# SCH_tec-APUS_7_2022-02-12.net
KiCad netlist of a schematic drawn in EasyEDA
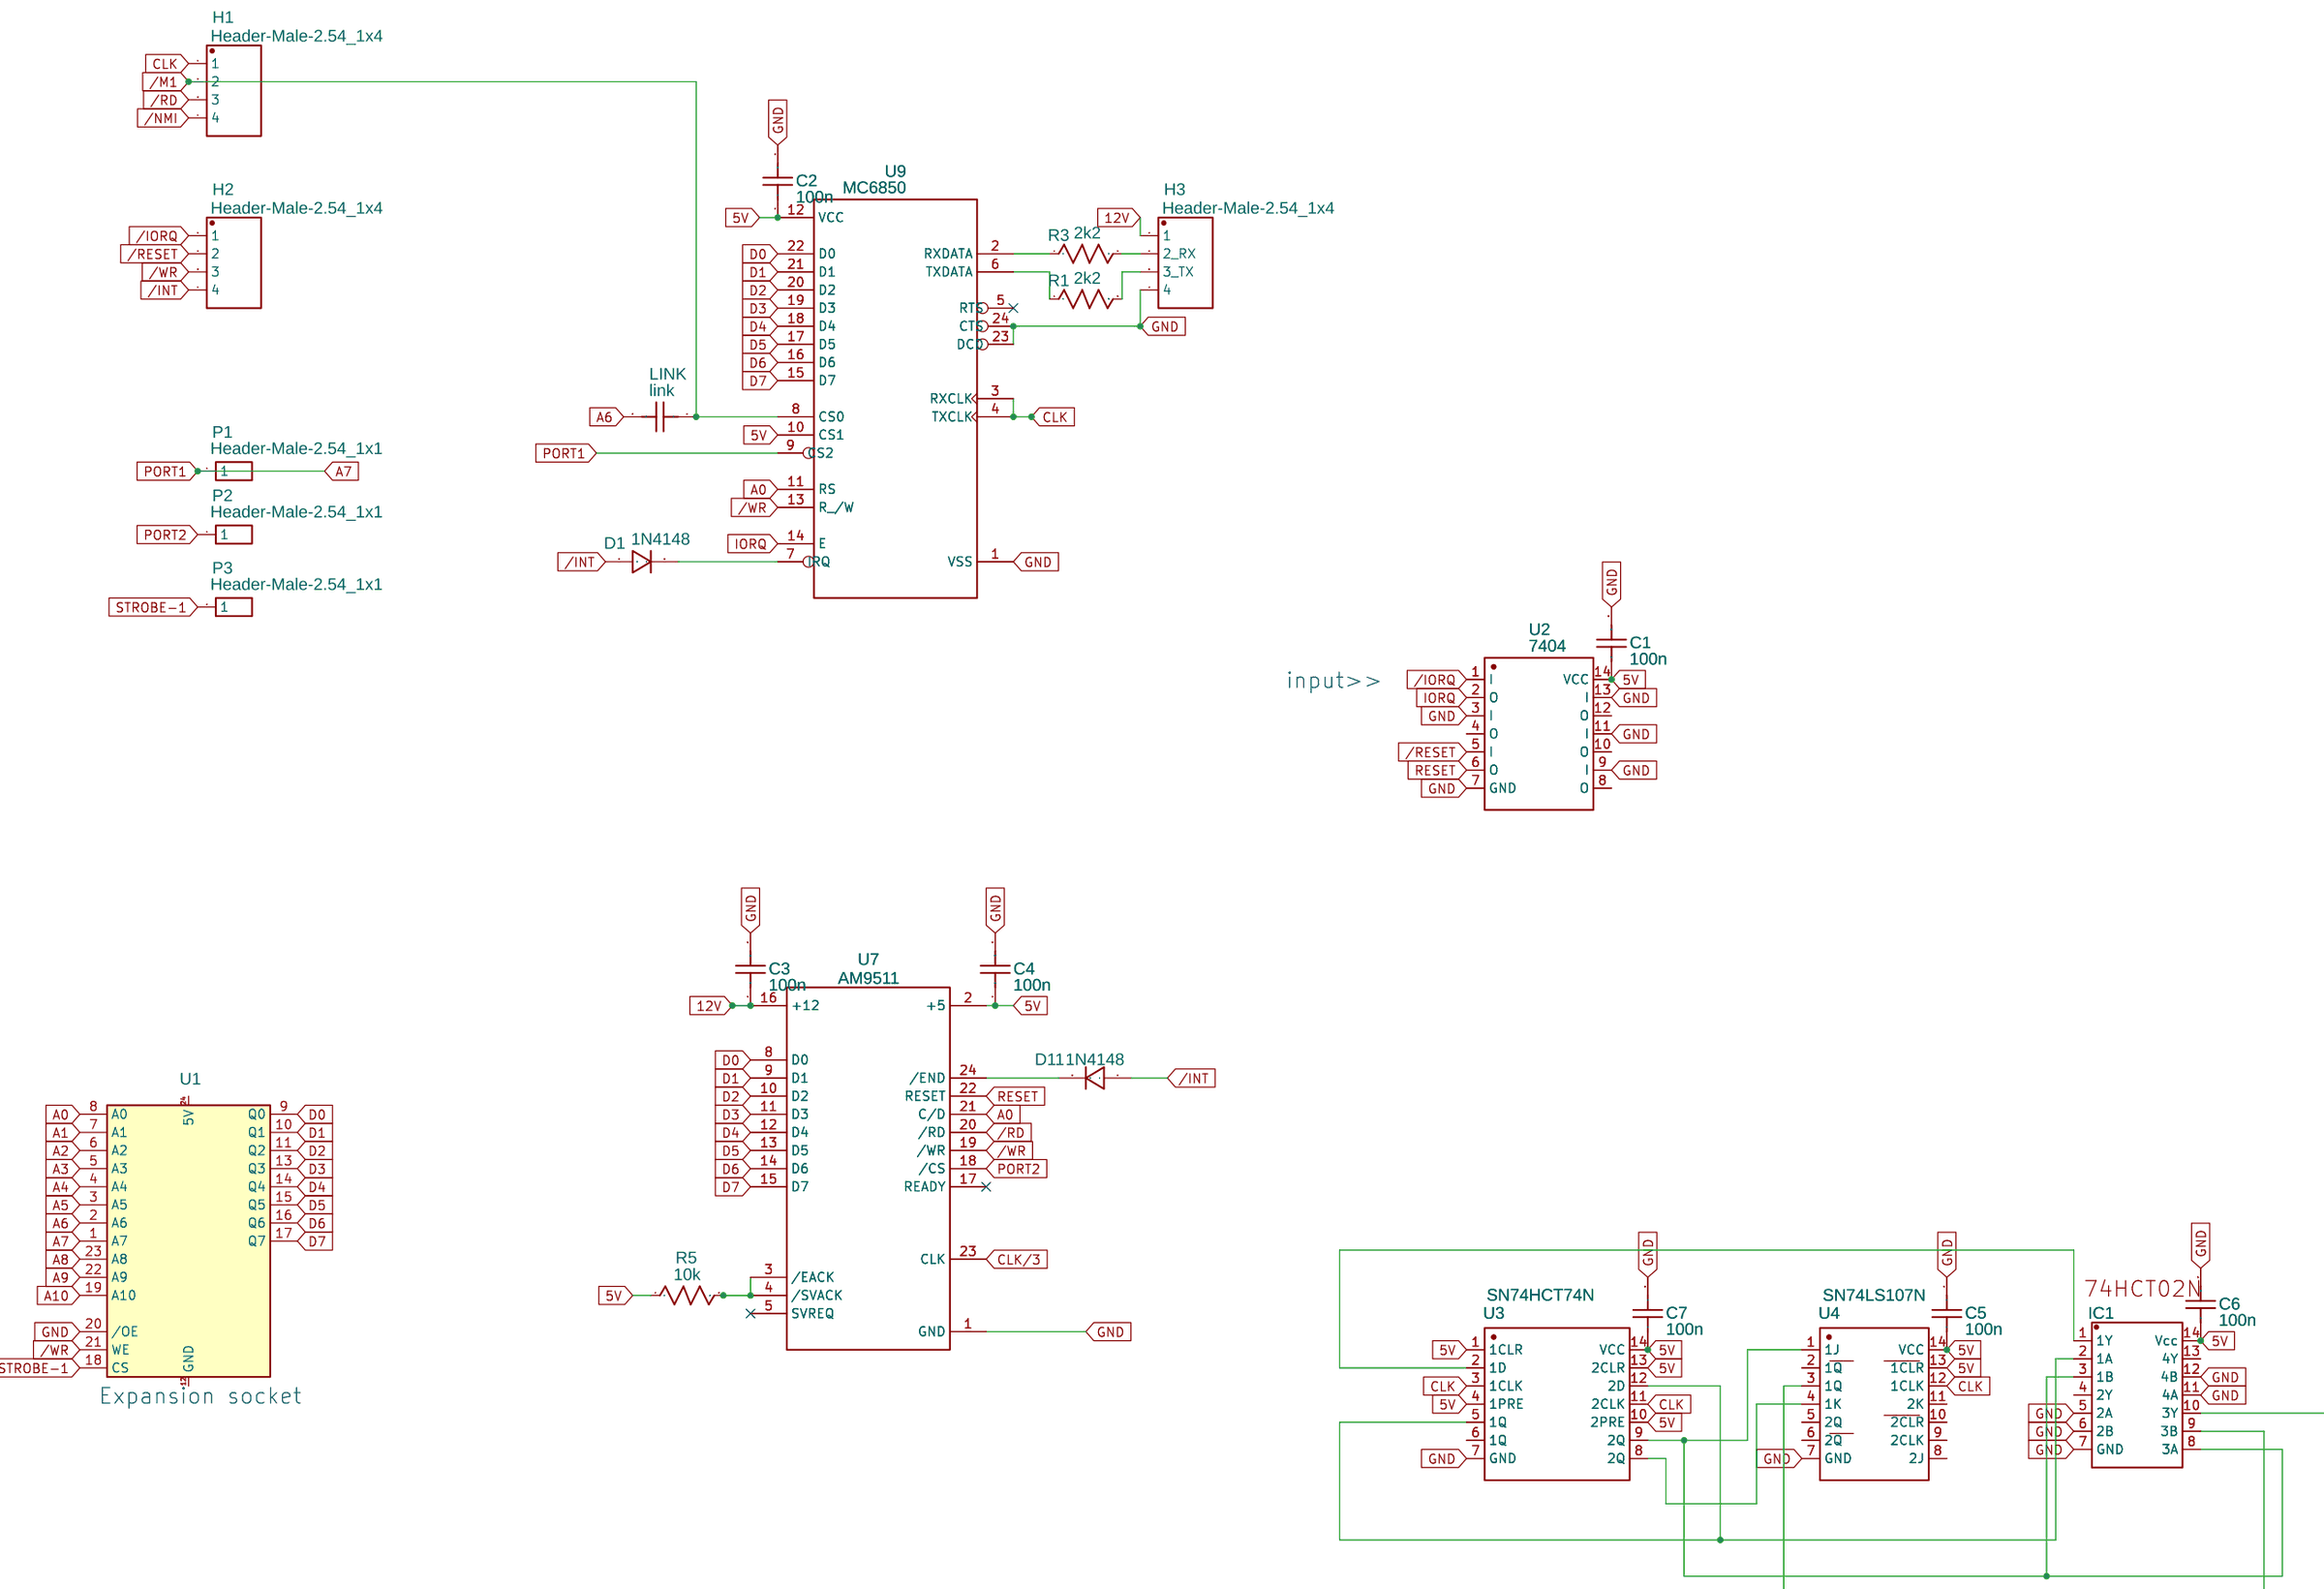
[diagram p0: schematic sheet]

(export (version "E")
  (design (tool "Eeschema 10.0.6"))
  (components
    (comp (ref "C1") (value "100n") (libsource (lib "") (part "C_RAD-0.1_US_1")))
    (comp (ref "C2") (value "100n") (libsource (lib "") (part "C_RAD-0.1_US_1")))
    (comp (ref "C3") (value "100n") (libsource (lib "") (part "C_RAD-0.1_US_1")))
    (comp (ref "C4") (value "100n") (libsource (lib "") (part "C_RAD-0.1_US_1")))
    (comp (ref "C5") (value "100n") (libsource (lib "") (part "C_RAD-0.1_US_1")))
    (comp (ref "C6") (value "100n") (libsource (lib "") (part "C_RAD-0.1_US_1")))
    (comp (ref "C7") (value "100n") (libsource (lib "") (part "C_RAD-0.1_US_1")))
    (comp (ref "D1")
      (value "1N4148")
      (fields (field (name "BOM_Manufacturer Part") "1N4448") (field (name "BOM_Supplier Part") "C54037"))
      (libsource (lib "") (part "Unknown_490_-415"))
    )
    (comp (ref "D11")
      (value "1N4148")
      (fields (field (name "BOM_Manufacturer Part") "1N4448") (field (name "BOM_Supplier Part") "C54037"))
      (libsource (lib "") (part "Unknown_740_-130"))
    )
    (comp (ref "H1")
      (value "Header-Male-2.54_1x4")
      (fields
        (field (name "BOM_Manufacturer Part") "210S-1*4P L=11.6MMGold-plated black")
        (field (name "BOM_Supplier Part") "C124378")
      )
      (libsource (lib "") (part "Header-Male-2.54_1x4"))
    )
    (comp (ref "H2")
      (value "Header-Male-2.54_1x4")
      (fields
        (field (name "BOM_Manufacturer Part") "210S-1*4P L=11.6MMGold-plated black")
        (field (name "BOM_Supplier Part") "C124378")
      )
      (libsource (lib "") (part "Header-Male-2.54_1x4"))
    )
    (comp (ref "H3")
      (value "Header-Male-2.54_1x4")
      (fields
        (field (name "BOM_Manufacturer Part") "210S-1*4P L=11.6MMGold-plated black")
        (field (name "BOM_Supplier Part") "C124378")
      )
      (libsource (lib "") (part "Header-Male-2.54_1x4_1"))
    )
    (comp (ref "IC1") (value "x74HCT02N") (libsource (lib "") (part "x74HCT02N")))
    (comp (ref "LINK") (value "link") (libsource (lib "") (part "C_RAD-0.1_US")))
    (comp (ref "P1")
      (value "Header-Male-2.54_1x1")
      (fields (field (name "BOM_Supplier Part") "C81276"))
      (libsource (lib "") (part "Header-Male-2.54_1x1"))
    )
    (comp (ref "P2")
      (value "Header-Male-2.54_1x1")
      (fields (field (name "BOM_Supplier Part") "C81276"))
      (libsource (lib "") (part "Header-Male-2.54_1x1"))
    )
    (comp (ref "P3")
      (value "Header-Male-2.54_1x1")
      (fields (field (name "BOM_Supplier Part") "C81276"))
      (libsource (lib "") (part "Header-Male-2.54_1x1"))
    )
    (comp (ref "R1") (value "2k2") (libsource (lib "") (part "R_AXIAL-0.3_US")))
    (comp (ref "R3") (value "2k2") (libsource (lib "") (part "R_AXIAL-0.3_US")))
    (comp (ref "R5") (value "10k") (libsource (lib "") (part "R_AXIAL-0.3_US")))
    (comp (ref "U1")
      (value "6116")
      (fields (field (name "BOM_Manufacturer Part") "?"))
      (libsource (lib "") (part "Unknown_240_-40"))
    )
    (comp (ref "U2") (value "7404") (libsource (lib "") (part "7404")))
    (comp (ref "U3") (value "SN74HCT74N") (libsource (lib "") (part "SN74HCT74N")))
    (comp (ref "U4")
      (value "SN74LS107N")
      (fields (field (name "BOM_Supplier Part") "C5262"))
      (libsource (lib "") (part "SN74LS107N"))
    )
    (comp (ref "U7") (value "AM9511") (libsource (lib "") (part "AM9511")))
    (comp (ref "U9")
      (value "MC6850")
      (fields (field (name "BOM_Manufacturer Part") "?"))
      (libsource (lib "") (part "Unknown_635_-505"))
    )
  )
  (nets
    (net (code "1") (name "5V") (class "Default")
      (node (ref "C1") (pin "1") (pinfunction "1_1") (pintype "unspecified"))
      (node (ref "C2") (pin "1") (pinfunction "1_1") (pintype "unspecified"))
      (node (ref "C4") (pin "1") (pinfunction "1_1") (pintype "unspecified"))
      (node (ref "C5") (pin "1") (pinfunction "1_1") (pintype "unspecified"))
      (node (ref "C6") (pin "1") (pinfunction "1_1") (pintype "unspecified"))
      (node (ref "C7") (pin "1") (pinfunction "1_1") (pintype "unspecified"))
      (node (ref "IC1") (pin "14") (pinfunction "Vcc_14") (pintype "unspecified"))
      (node (ref "R5") (pin "1") (pinfunction "1_1") (pintype "unspecified"))
      (node (ref "U2") (pin "14") (pinfunction "VCC_14") (pintype "unspecified"))
      (node (ref "U3") (pin "1") (pinfunction "1CLR_1") (pintype "unspecified"))
      (node (ref "U3") (pin "10") (pinfunction "2PRE_10") (pintype "unspecified"))
      (node (ref "U3") (pin "13") (pinfunction "2CLR_13") (pintype "unspecified"))
      (node (ref "U3") (pin "14") (pinfunction "VCC_14") (pintype "unspecified"))
      (node (ref "U3") (pin "4") (pinfunction "1PRE_4") (pintype "unspecified"))
      (node (ref "U4") (pin "13") (pinfunction "1CLR_13") (pintype "unspecified"))
      (node (ref "U4") (pin "14") (pinfunction "VCC_14") (pintype "unspecified"))
      (node (ref "U7") (pin "2") (pinfunction "+5_2") (pintype "unspecified"))
      (node (ref "U9") (pin "10") (pinfunction "CS1_10") (pintype "input"))
      (node (ref "U9") (pin "12") (pinfunction "VCC_12") (pintype "passive"))
    )
    (net (code "2") (name "12V") (class "Default")
      (node (ref "C3") (pin "1") (pinfunction "1_1") (pintype "unspecified"))
      (node (ref "H3") (pin "1") (pinfunction "1_1") (pintype "unspecified"))
      (node (ref "U7") (pin "16") (pinfunction "+12_16") (pintype "unspecified"))
    )
    (net (code "3") (name "A0") (class "Default")
      (node (ref "U1") (pin "8") (pinfunction "A0_8") (pintype "input"))
      (node (ref "U7") (pin "21") (pinfunction "C/D_21") (pintype "unspecified"))
      (node (ref "U9") (pin "11") (pinfunction "RS_11") (pintype "input"))
    )
    (net (code "4") (name "A1") (class "Default")
      (node (ref "U1") (pin "7") (pinfunction "A1_7") (pintype "input"))
    )
    (net (code "5") (name "A2") (class "Default")
      (node (ref "U1") (pin "6") (pinfunction "A2_6") (pintype "input"))
    )
    (net (code "6") (name "A3") (class "Default")
      (node (ref "U1") (pin "5") (pinfunction "A3_5") (pintype "input"))
    )
    (net (code "7") (name "A4") (class "Default")
      (node (ref "U1") (pin "4") (pinfunction "A4_4") (pintype "input"))
    )
    (net (code "8") (name "A5") (class "Default")
      (node (ref "U1") (pin "3") (pinfunction "A5_3") (pintype "input"))
    )
    (net (code "9") (name "A6") (class "Default")
      (node (ref "LINK") (pin "2") (pinfunction "2_2") (pintype "unspecified"))
      (node (ref "U1") (pin "2") (pinfunction "A6_2") (pintype "input"))
    )
    (net (code "10") (name "A7") (class "Default")
      (node (ref "P1") (pin "1") (pinfunction "1_1") (pintype "input"))
      (node (ref "U1") (pin "1") (pinfunction "A7_1") (pintype "input"))
      (node (ref "U9") (pin "9") (pinfunction "CS2_9") (pintype "input"))
    )
    (net (code "11") (name "A8") (class "Default")
      (node (ref "U1") (pin "23") (pinfunction "A8_23") (pintype "input"))
    )
    (net (code "12") (name "A9") (class "Default")
      (node (ref "U1") (pin "22") (pinfunction "A9_22") (pintype "input"))
    )
    (net (code "13") (name "A10") (class "Default")
      (node (ref "U1") (pin "19") (pinfunction "A10_19") (pintype "input"))
    )
    (net (code "14") (name "CLK") (class "Default")
      (node (ref "H1") (pin "1") (pinfunction "1_1") (pintype "unspecified"))
      (node (ref "U3") (pin "11") (pinfunction "2CLK_11") (pintype "unspecified"))
      (node (ref "U3") (pin "3") (pinfunction "1CLK_3") (pintype "unspecified"))
      (node (ref "U4") (pin "12") (pinfunction "1CLK_12") (pintype "unspecified"))
      (node (ref "U9") (pin "3") (pinfunction "RXCLK_3") (pintype "input"))
      (node (ref "U9") (pin "4") (pinfunction "TXCLK_4") (pintype "input"))
    )
    (net (code "15") (name "CLK{slash}3") (class "Default")
      (node (ref "IC1") (pin "10") (pinfunction "3Y_10") (pintype "unspecified"))
      (node (ref "U7") (pin "23") (pinfunction "CLK_23") (pintype "unspecified"))
    )
    (net (code "16") (name "D0") (class "Default")
      (node (ref "U1") (pin "9") (pinfunction "Q0_9") (pintype "bidirectional"))
      (node (ref "U7") (pin "8") (pinfunction "D0_8") (pintype "unspecified"))
      (node (ref "U9") (pin "22") (pinfunction "D0_22") (pintype "unspecified"))
    )
    (net (code "17") (name "D1") (class "Default")
      (node (ref "U1") (pin "10") (pinfunction "Q1_10") (pintype "bidirectional"))
      (node (ref "U7") (pin "9") (pinfunction "D1_9") (pintype "unspecified"))
      (node (ref "U9") (pin "21") (pinfunction "D1_21") (pintype "unspecified"))
    )
    (net (code "18") (name "D2") (class "Default")
      (node (ref "U1") (pin "11") (pinfunction "Q2_11") (pintype "bidirectional"))
      (node (ref "U7") (pin "10") (pinfunction "D2_10") (pintype "unspecified"))
      (node (ref "U9") (pin "20") (pinfunction "D2_20") (pintype "unspecified"))
    )
    (net (code "19") (name "D3") (class "Default")
      (node (ref "U1") (pin "13") (pinfunction "Q3_13") (pintype "bidirectional"))
      (node (ref "U7") (pin "11") (pinfunction "D3_11") (pintype "unspecified"))
      (node (ref "U9") (pin "19") (pinfunction "D3_19") (pintype "unspecified"))
    )
    (net (code "20") (name "D4") (class "Default")
      (node (ref "U1") (pin "14") (pinfunction "Q4_14") (pintype "bidirectional"))
      (node (ref "U7") (pin "12") (pinfunction "D4_12") (pintype "unspecified"))
      (node (ref "U9") (pin "18") (pinfunction "D4_18") (pintype "unspecified"))
    )
    (net (code "21") (name "D5") (class "Default")
      (node (ref "U1") (pin "15") (pinfunction "Q5_15") (pintype "bidirectional"))
      (node (ref "U7") (pin "13") (pinfunction "D5_13") (pintype "unspecified"))
      (node (ref "U9") (pin "17") (pinfunction "D5_17") (pintype "unspecified"))
    )
    (net (code "22") (name "D6") (class "Default")
      (node (ref "U1") (pin "16") (pinfunction "Q6_16") (pintype "bidirectional"))
      (node (ref "U7") (pin "14") (pinfunction "D6_14") (pintype "unspecified"))
      (node (ref "U9") (pin "16") (pinfunction "D6_16") (pintype "unspecified"))
    )
    (net (code "23") (name "D7") (class "Default")
      (node (ref "U1") (pin "17") (pinfunction "Q7_17") (pintype "bidirectional"))
      (node (ref "U7") (pin "15") (pinfunction "D7_15") (pintype "unspecified"))
      (node (ref "U9") (pin "15") (pinfunction "D7_15") (pintype "unspecified"))
    )
    (net (code "24") (name "GND") (class "Default")
      (node (ref "C1") (pin "2") (pinfunction "2_2") (pintype "unspecified"))
      (node (ref "C2") (pin "2") (pinfunction "2_2") (pintype "unspecified"))
      (node (ref "C3") (pin "2") (pinfunction "2_2") (pintype "unspecified"))
      (node (ref "C4") (pin "2") (pinfunction "2_2") (pintype "unspecified"))
      (node (ref "C5") (pin "2") (pinfunction "2_2") (pintype "unspecified"))
      (node (ref "C6") (pin "2") (pinfunction "2_2") (pintype "unspecified"))
      (node (ref "C7") (pin "2") (pinfunction "2_2") (pintype "unspecified"))
      (node (ref "H3") (pin "4") (pinfunction "4_4") (pintype "unspecified"))
      (node (ref "IC1") (pin "11") (pinfunction "4A_11") (pintype "unspecified"))
      (node (ref "IC1") (pin "12") (pinfunction "4B_12") (pintype "unspecified"))
      (node (ref "IC1") (pin "5") (pinfunction "2A_5") (pintype "unspecified"))
      (node (ref "IC1") (pin "6") (pinfunction "2B_6") (pintype "unspecified"))
      (node (ref "IC1") (pin "7") (pinfunction "GND_7") (pintype "unspecified"))
      (node (ref "U1") (pin "20") (pinfunction "/OE_20") (pintype "input"))
      (node (ref "U2") (pin "11") (pinfunction "I_11") (pintype "unspecified"))
      (node (ref "U2") (pin "13") (pinfunction "I_13") (pintype "unspecified"))
      (node (ref "U2") (pin "3") (pinfunction "I_3") (pintype "unspecified"))
      (node (ref "U2") (pin "7") (pinfunction "GND_7") (pintype "unspecified"))
      (node (ref "U2") (pin "9") (pinfunction "I_9") (pintype "unspecified"))
      (node (ref "U3") (pin "7") (pinfunction "GND_7") (pintype "unspecified"))
      (node (ref "U4") (pin "7") (pinfunction "GND_7") (pintype "unspecified"))
      (node (ref "U7") (pin "1") (pinfunction "GND_1") (pintype "unspecified"))
      (node (ref "U9") (pin "1") (pinfunction "VSS_1") (pintype "passive"))
      (node (ref "U9") (pin "23") (pinfunction "DCD_23") (pintype "input"))
      (node (ref "U9") (pin "24") (pinfunction "CTS_24") (pintype "input"))
    )
    (net (code "25") (name "IORQ") (class "Default")
      (node (ref "U2") (pin "2") (pinfunction "O_2") (pintype "unspecified"))
      (node (ref "U9") (pin "14") (pinfunction "E_14") (pintype "input"))
    )
    (net (code "26") (name "Net-(D1-K)") (class "Default")
      (node (ref "D1") (pin "2") (pinfunction "K_2") (pintype "unspecified"))
      (node (ref "U9") (pin "7") (pinfunction "IRQ_7") (pintype "output"))
    )
    (net (code "27") (name "Net-(D11-K)") (class "Default")
      (node (ref "D11") (pin "2") (pinfunction "K_2") (pintype "unspecified"))
      (node (ref "U7") (pin "24") (pinfunction "/END_24") (pintype "unspecified"))
    )
    (net (code "28") (name "Net-(H3-2_RX)") (class "Default")
      (node (ref "H3") (pin "2") (pinfunction "2_RX_2") (pintype "unspecified"))
      (node (ref "R3") (pin "2") (pinfunction "2_2") (pintype "unspecified"))
    )
    (net (code "29") (name "Net-(H3-3_TX)") (class "Default")
      (node (ref "H3") (pin "3") (pinfunction "3_TX_3") (pintype "unspecified"))
      (node (ref "R1") (pin "2") (pinfunction "2_2") (pintype "unspecified"))
    )
    (net (code "30") (name "Net-(IC1-1A)") (class "Default")
      (node (ref "IC1") (pin "2") (pinfunction "1A_2") (pintype "unspecified"))
      (node (ref "U3") (pin "12") (pinfunction "2D_12") (pintype "unspecified"))
      (node (ref "U3") (pin "5") (pinfunction "1Q_5") (pintype "unspecified"))
    )
    (net (code "31") (name "Net-(IC1-1B)") (class "Default")
      (node (ref "IC1") (pin "3") (pinfunction "1B_3") (pintype "unspecified"))
      (node (ref "IC1") (pin "8") (pinfunction "3A_8") (pintype "unspecified"))
      (node (ref "U3") (pin "9") (pinfunction "2Q_9") (pintype "unspecified"))
      (node (ref "U4") (pin "1") (pinfunction "1J_1") (pintype "unspecified"))
    )
    (net (code "32") (name "Net-(IC1-1Y)") (class "Default")
      (node (ref "IC1") (pin "1") (pinfunction "1Y_1") (pintype "unspecified"))
      (node (ref "U3") (pin "2") (pinfunction "1D_2") (pintype "unspecified"))
    )
    (net (code "33") (name "Net-(IC1-3B)") (class "Default")
      (node (ref "IC1") (pin "9") (pinfunction "3B_9") (pintype "unspecified"))
      (node (ref "U4") (pin "3") (pinfunction "1Q_3") (pintype "unspecified"))
    )
    (net (code "34") (name "Net-(U4-1K)") (class "Default")
      (node (ref "U3") (pin "8") (pinfunction "2Q_8") (pintype "unspecified"))
      (node (ref "U4") (pin "4") (pinfunction "1K_4") (pintype "unspecified"))
    )
    (net (code "35") (name "Net-(U7-{slash}EACK)") (class "Default")
      (node (ref "R5") (pin "2") (pinfunction "2_2") (pintype "unspecified"))
      (node (ref "U7") (pin "3") (pinfunction "/EACK_3") (pintype "unspecified"))
      (node (ref "U7") (pin "4") (pinfunction "/SVACK_4") (pintype "unspecified"))
    )
    (net (code "36") (name "Net-(U9-RXDATA)") (class "Default")
      (node (ref "R3") (pin "1") (pinfunction "1_1") (pintype "unspecified"))
      (node (ref "U9") (pin "2") (pinfunction "RXDATA_2") (pintype "input"))
    )
    (net (code "37") (name "Net-(U9-TXDATA)") (class "Default")
      (node (ref "R1") (pin "1") (pinfunction "1_1") (pintype "unspecified"))
      (node (ref "U9") (pin "6") (pinfunction "TXDATA_6") (pintype "output"))
    )
    (net (code "38") (name "PORT2") (class "Default")
      (node (ref "P2") (pin "1") (pinfunction "1_1") (pintype "input"))
      (node (ref "U7") (pin "18") (pinfunction "/CS_18") (pintype "unspecified"))
    )
    (net (code "39") (name "RESET") (class "Default")
      (node (ref "U2") (pin "6") (pinfunction "O_6") (pintype "unspecified"))
      (node (ref "U7") (pin "22") (pinfunction "RESET_22") (pintype "unspecified"))
    )
    (net (code "40") (name "STROBE-1") (class "Default")
      (node (ref "P3") (pin "1") (pinfunction "1_1") (pintype "input"))
      (node (ref "U1") (pin "18") (pinfunction "CS_18") (pintype "input"))
    )
    (net (code "41") (name "unconnected-(IC1-2Y-Pad4)") (class "Default")
      (node (ref "IC1") (pin "4") (pinfunction "2Y_4") (pintype "unspecified"))
    )
    (net (code "42") (name "unconnected-(IC1-4Y-Pad13)") (class "Default")
      (node (ref "IC1") (pin "13") (pinfunction "4Y_13") (pintype "unspecified"))
    )
    (net (code "43") (name "unconnected-(U1-5V-Pad24)") (class "Default")
      (node (ref "U1") (pin "24") (pinfunction "5V_24") (pintype "bidirectional"))
    )
    (net (code "44") (name "unconnected-(U1-GND-Pad12)") (class "Default")
      (node (ref "U1") (pin "12") (pinfunction "GND_12") (pintype "bidirectional"))
    )
    (net (code "45") (name "unconnected-(U2-O-Pad4)") (class "Default")
      (node (ref "U2") (pin "4") (pinfunction "O_4") (pintype "unspecified"))
    )
    (net (code "46") (name "unconnected-(U2-O-Pad8)") (class "Default")
      (node (ref "U2") (pin "8") (pinfunction "O_8") (pintype "unspecified"))
    )
    (net (code "47") (name "unconnected-(U2-O-Pad10)") (class "Default")
      (node (ref "U2") (pin "10") (pinfunction "O_10") (pintype "unspecified"))
    )
    (net (code "48") (name "unconnected-(U2-O-Pad12)") (class "Default")
      (node (ref "U2") (pin "12") (pinfunction "O_12") (pintype "unspecified"))
    )
    (net (code "49") (name "unconnected-(U3-1Q-Pad6)") (class "Default")
      (node (ref "U3") (pin "6") (pinfunction "1Q_6") (pintype "unspecified"))
    )
    (net (code "50") (name "unconnected-(U4-1Q-Pad2)") (class "Default")
      (node (ref "U4") (pin "2") (pinfunction "1Q_2") (pintype "unspecified"))
    )
    (net (code "51") (name "unconnected-(U4-2CLK-Pad9)") (class "Default")
      (node (ref "U4") (pin "9") (pinfunction "2CLK_9") (pintype "unspecified"))
    )
    (net (code "52") (name "unconnected-(U4-2CLR-Pad10)") (class "Default")
      (node (ref "U4") (pin "10") (pinfunction "2CLR_10") (pintype "unspecified"))
    )
    (net (code "53") (name "unconnected-(U4-2J-Pad8)") (class "Default")
      (node (ref "U4") (pin "8") (pinfunction "2J_8") (pintype "unspecified"))
    )
    (net (code "54") (name "unconnected-(U4-2K-Pad11)") (class "Default")
      (node (ref "U4") (pin "11") (pinfunction "2K_11") (pintype "unspecified"))
    )
    (net (code "55") (name "unconnected-(U4-2Q-Pad5)") (class "Default")
      (node (ref "U4") (pin "5") (pinfunction "2Q_5") (pintype "unspecified"))
    )
    (net (code "56") (name "unconnected-(U4-2Q-Pad6)") (class "Default")
      (node (ref "U4") (pin "6") (pinfunction "2Q_6") (pintype "unspecified"))
    )
    (net (code "57") (name "unconnected-(U7-READY-Pad17)") (class "Default")
      (node (ref "U7") (pin "17") (pinfunction "READY_17") (pintype "unspecified+no_connect"))
    )
    (net (code "58") (name "unconnected-(U7-SVREQ-Pad5)") (class "Default")
      (node (ref "U7") (pin "5") (pinfunction "SVREQ_5") (pintype "unspecified+no_connect"))
    )
    (net (code "59") (name "unconnected-(U9-RTS-Pad5)") (class "Default")
      (node (ref "U9") (pin "5") (pinfunction "RTS_5") (pintype "output+no_connect"))
    )
    (net (code "60") (name "{slash}INT") (class "Default")
      (node (ref "D1") (pin "1") (pinfunction "A_1") (pintype "unspecified"))
      (node (ref "D11") (pin "1") (pinfunction "A_1") (pintype "unspecified"))
      (node (ref "H2") (pin "4") (pinfunction "4_4") (pintype "unspecified"))
    )
    (net (code "61") (name "{slash}IORQ") (class "Default")
      (node (ref "H2") (pin "1") (pinfunction "1_1") (pintype "unspecified"))
      (node (ref "U2") (pin "1") (pinfunction "I_1") (pintype "unspecified"))
    )
    (net (code "62") (name "{slash}M1") (class "Default")
      (node (ref "H1") (pin "2") (pinfunction "2_2") (pintype "unspecified"))
      (node (ref "LINK") (pin "1") (pinfunction "1_1") (pintype "unspecified"))
      (node (ref "U9") (pin "8") (pinfunction "CS0_8") (pintype "input"))
    )
    (net (code "63") (name "{slash}NMI") (class "Default")
      (node (ref "H1") (pin "4") (pinfunction "4_4") (pintype "unspecified"))
    )
    (net (code "64") (name "{slash}RD") (class "Default")
      (node (ref "H1") (pin "3") (pinfunction "3_3") (pintype "unspecified"))
      (node (ref "U7") (pin "20") (pinfunction "/RD_20") (pintype "unspecified"))
    )
    (net (code "65") (name "{slash}RESET") (class "Default")
      (node (ref "H2") (pin "2") (pinfunction "2_2") (pintype "unspecified"))
      (node (ref "U2") (pin "5") (pinfunction "I_5") (pintype "unspecified"))
    )
    (net (code "66") (name "{slash}WR") (class "Default")
      (node (ref "H2") (pin "3") (pinfunction "3_3") (pintype "unspecified"))
      (node (ref "U1") (pin "21") (pinfunction "WE_21") (pintype "input"))
      (node (ref "U7") (pin "19") (pinfunction "/WR_19") (pintype "unspecified"))
      (node (ref "U9") (pin "13") (pinfunction "R_/W_13") (pintype "input"))
    )
  )
)
